# Clock_Generator.net
KiCad netlist of a schematic drawn in Altium Designer
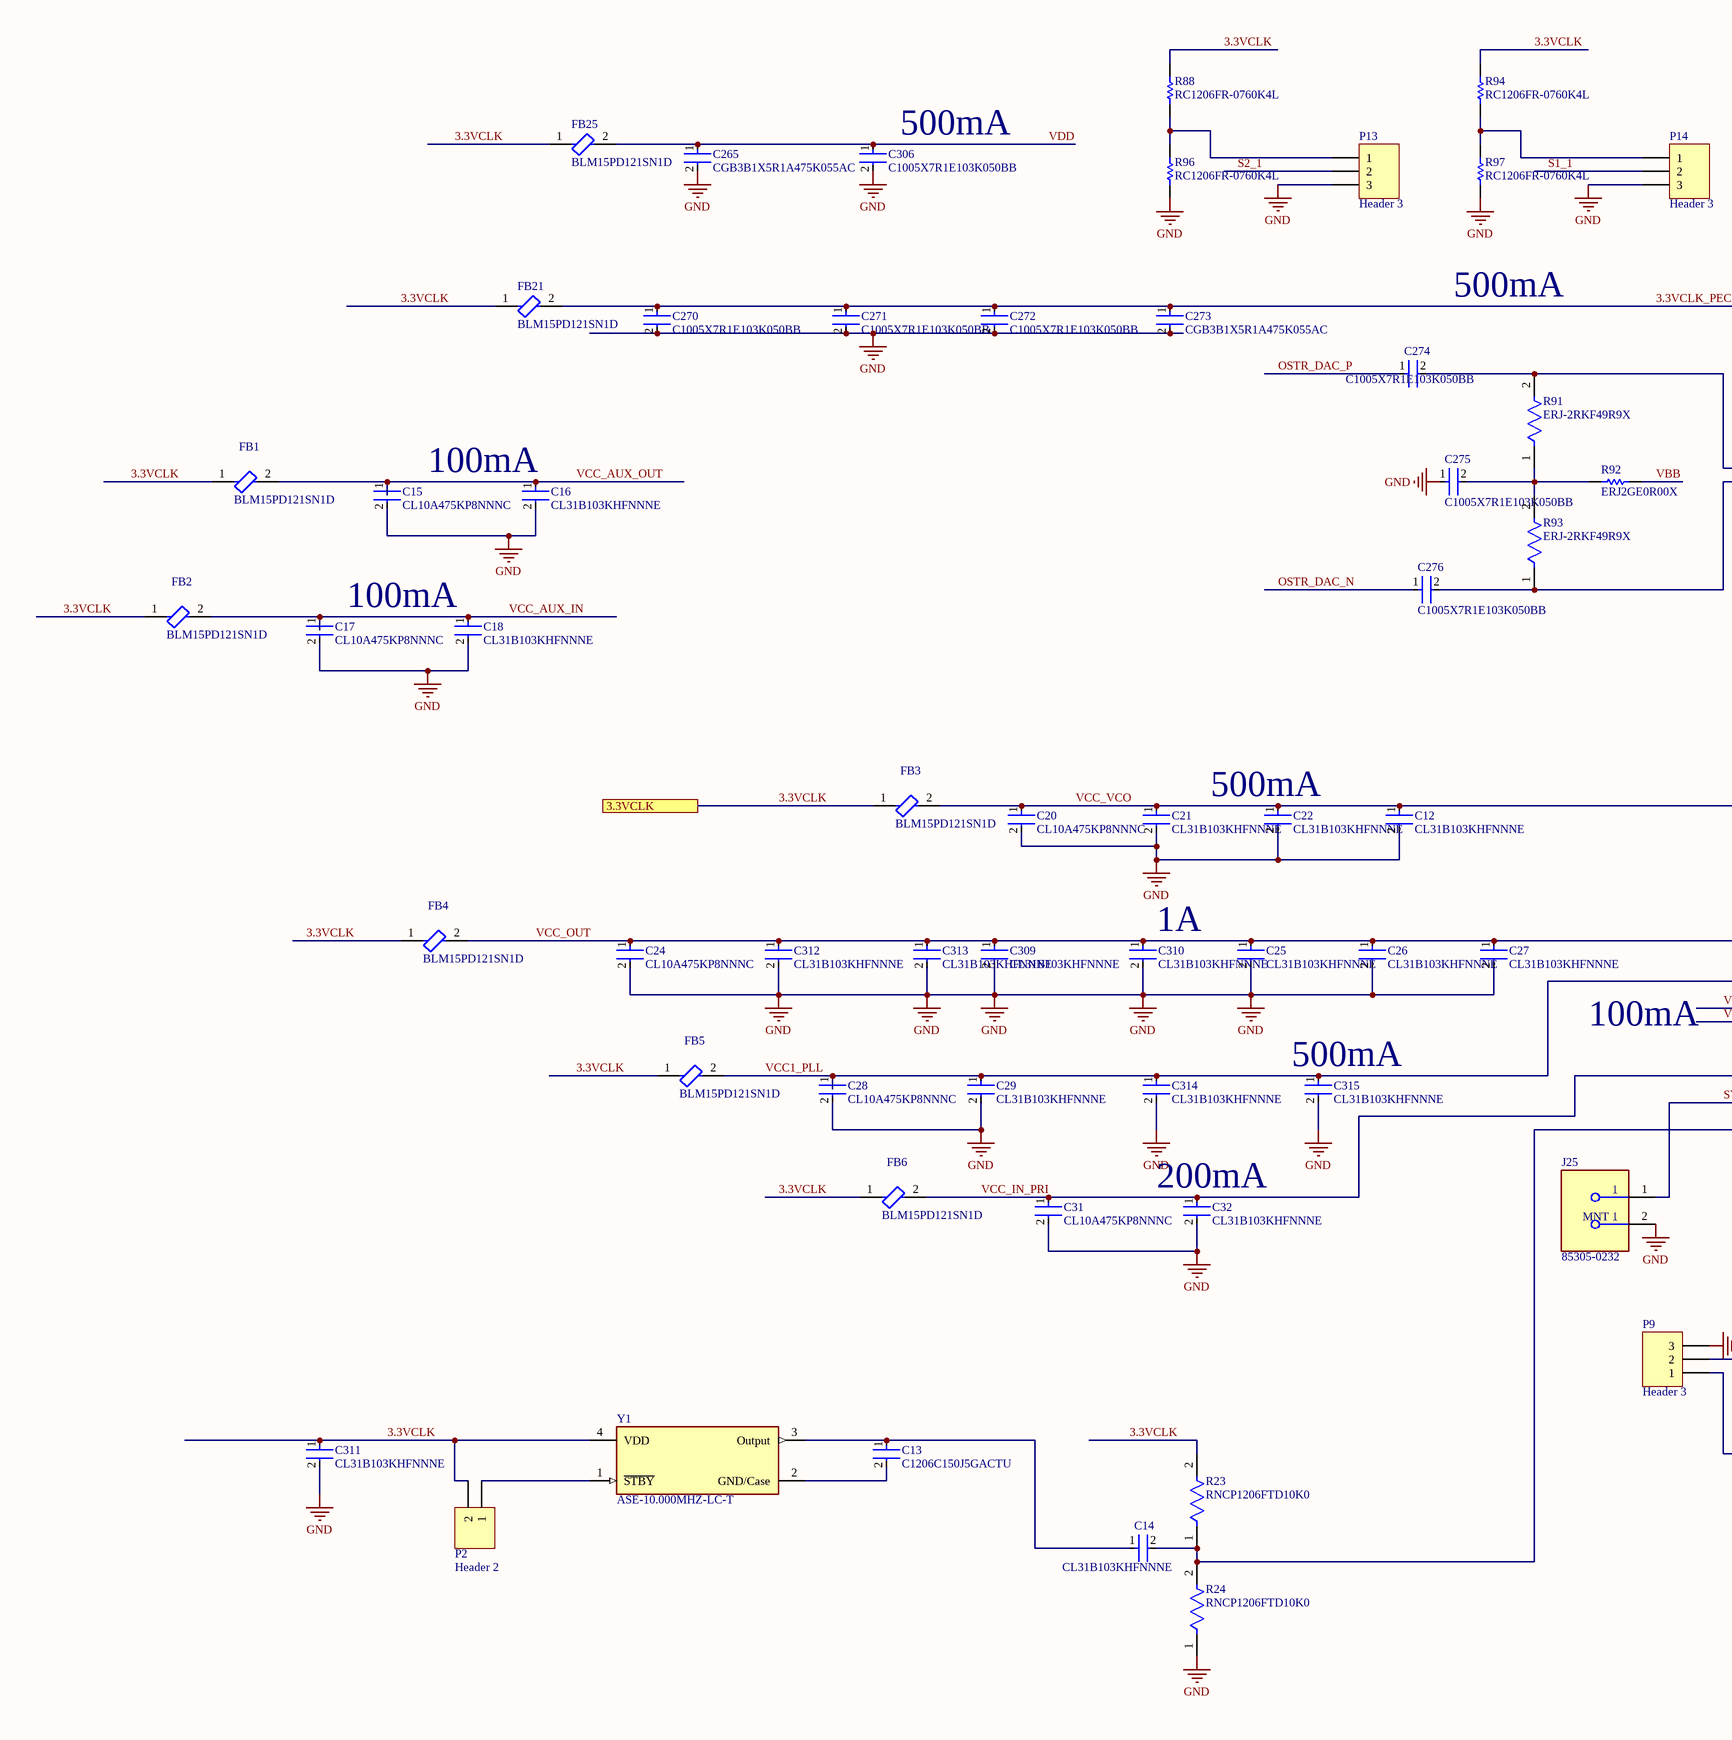
[diagram p0: Clock_Generator.SchDoc, left]
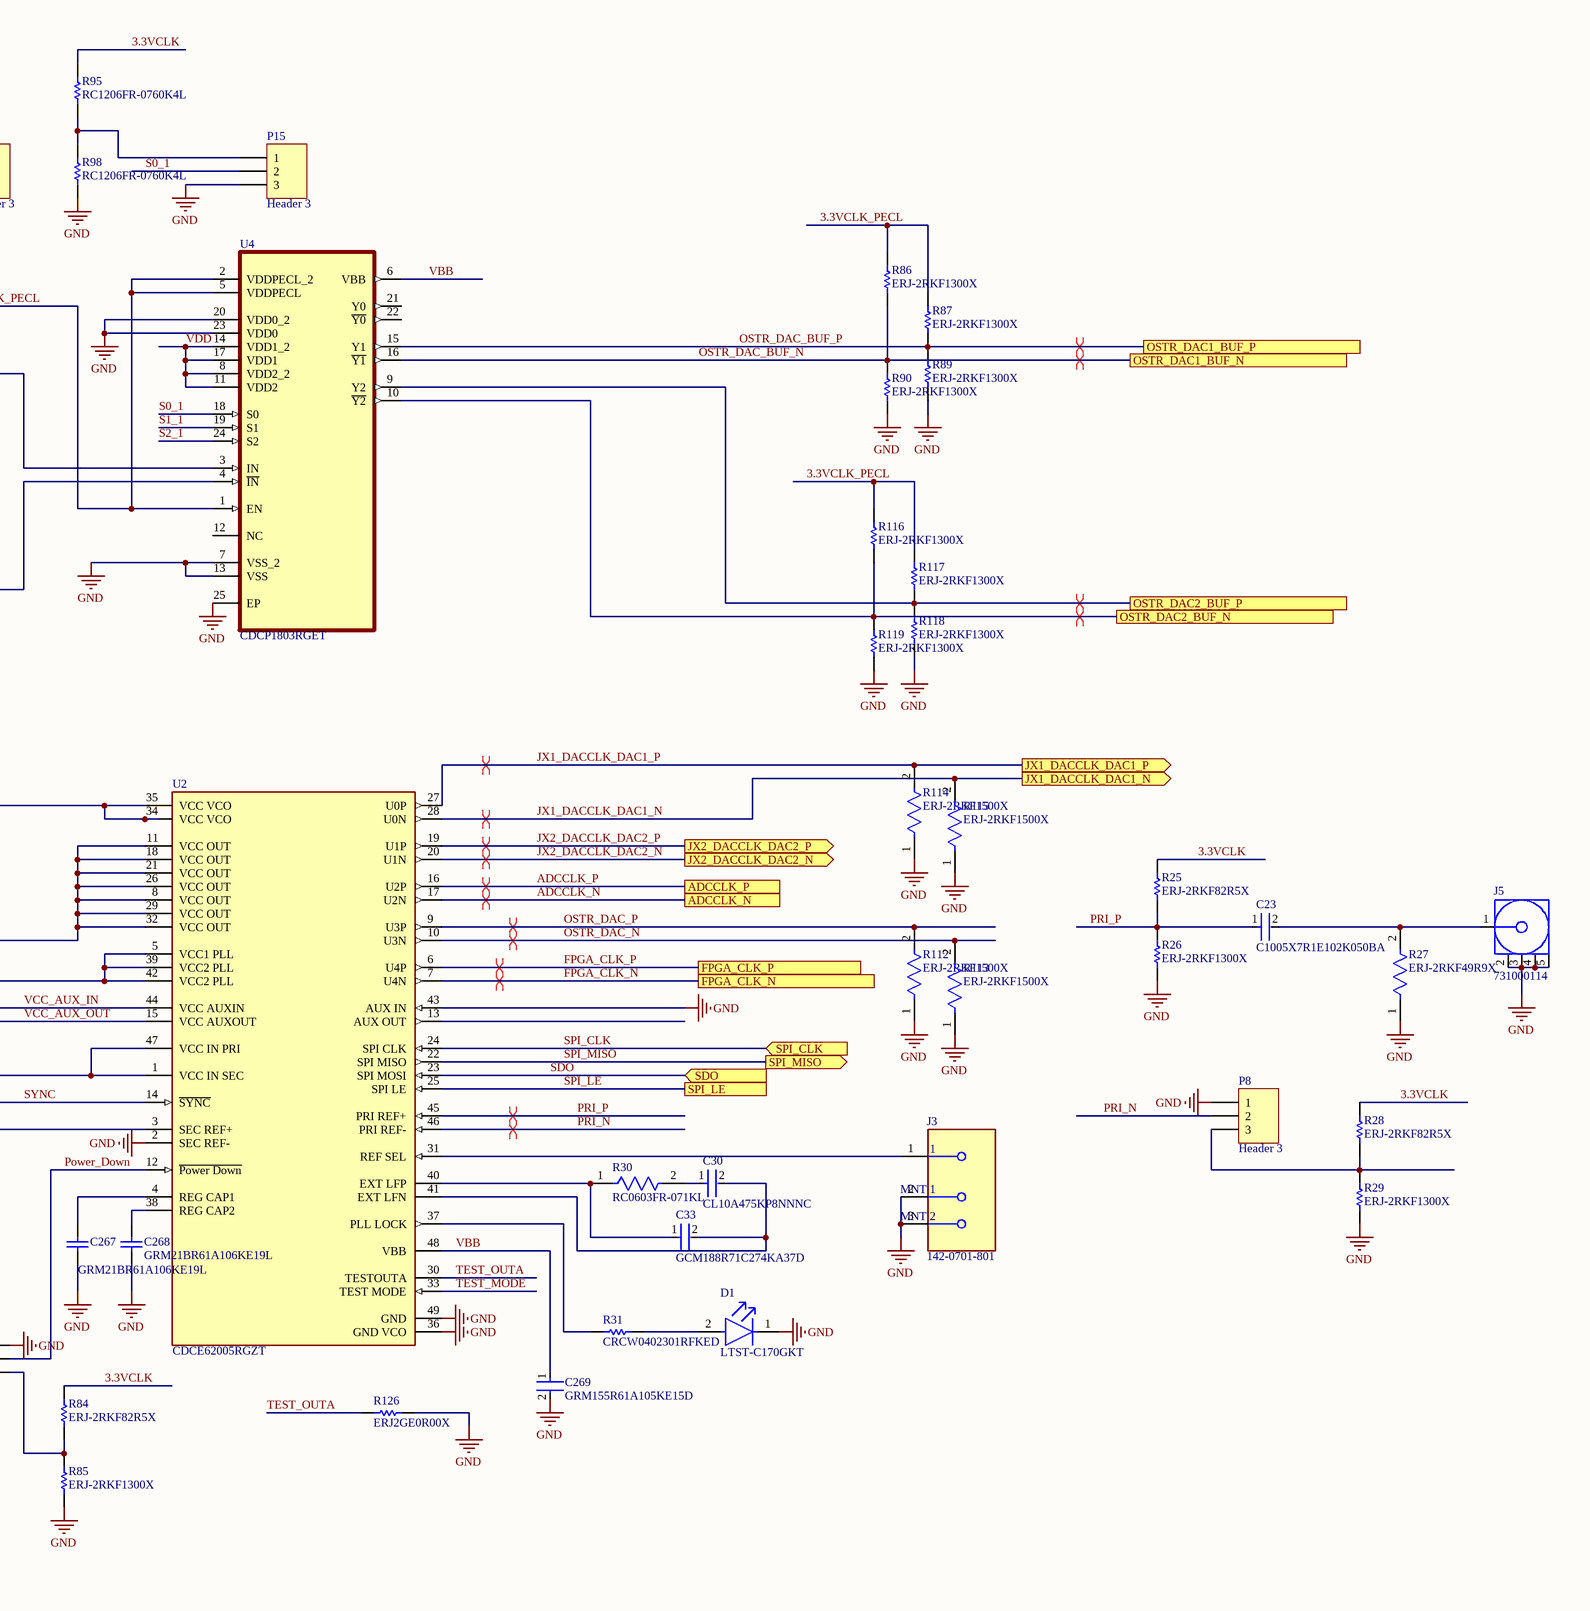
[diagram p1: Clock_Generator.SchDoc, right]

(export (version "E")
  (design (tool "Eeschema 10.0.6"))
  (components
    (comp (ref "C12")
      (value "CL31B103KHFNNNE")
      (footprint "C1206")
      (description "Cap Ceramic 10nF 630V X7R ±10% SMD 1206 +125°C Embossed T/R")
      (fields (field (name "TOLERANCE") "10%") (field (name "VOLTAGE") "630V"))
      (libsource (lib "DACֹֹ_Sources") (part "b4654b650e69147ec39a6b967a45e02"))
    )
    (comp (ref "C13")
      (value "C1206C150J5GACTU")
      (footprint "C1206")
      (description "1206 C 15pF Ceramic Multilayer Capacitor; 50 VDC; +125degC; C0G Dielec; +/-5%")
      (fields (field (name "TOLERANCE") "0.05") (field (name "MANUFACTURER") "KEMET"))
      (libsource (lib "DACֹֹ_Sources") (part "b4654b650e69147ec39a6b967a45e02"))
    )
    (comp (ref "C14")
      (value "CL31B103KHFNNNE")
      (footprint "C1206")
      (description "Cap Ceramic 10nF 630V X7R ±10% SMD 1206 +125°C Embossed T/R")
      (fields (field (name "TOLERANCE") "10%") (field (name "VOLTAGE") "630V"))
      (libsource (lib "DACֹֹ_Sources") (part "b4654b650e69147ec39a6b967a45e02"))
    )
    (comp (ref "C15")
      (value "CL10A475KP8NNNC")
      (footprint "C0603")
      (description "Cap Ceramic 4.7uF 10V X5R ±10% Pad SMD 0603 +85°C T/R")
      (fields (field (name "TOLERANCE") "10%"))
      (libsource (lib "DACֹֹ_Sources") (part "b4654b650e69147ec39a6b967a45e02"))
    )
    (comp (ref "C16")
      (value "CL31B103KHFNNNE")
      (footprint "C1206")
      (description "Cap Ceramic 10nF 630V X7R ±10% SMD 1206 +125°C Embossed T/R")
      (fields (field (name "TOLERANCE") "10%") (field (name "VOLTAGE") "630V"))
      (libsource (lib "DACֹֹ_Sources") (part "b4654b650e69147ec39a6b967a45e02"))
    )
    (comp (ref "C17")
      (value "CL10A475KP8NNNC")
      (footprint "C0603")
      (description "Cap Ceramic 4.7uF 10V X5R ±10% Pad SMD 0603 +85°C T/R")
      (fields (field (name "TOLERANCE") "10%"))
      (libsource (lib "DACֹֹ_Sources") (part "b4654b650e69147ec39a6b967a45e02"))
    )
    (comp (ref "C18")
      (value "CL31B103KHFNNNE")
      (footprint "C1206")
      (description "Cap Ceramic 10nF 630V X7R ±10% SMD 1206 +125°C Embossed T/R")
      (fields (field (name "TOLERANCE") "10%") (field (name "VOLTAGE") "630V"))
      (libsource (lib "DACֹֹ_Sources") (part "b4654b650e69147ec39a6b967a45e02"))
    )
    (comp (ref "C20")
      (value "CL10A475KP8NNNC")
      (footprint "C0603")
      (description "Cap Ceramic 4.7uF 10V X5R ±10% Pad SMD 0603 +85°C T/R")
      (fields (field (name "TOLERANCE") "10%"))
      (libsource (lib "DACֹֹ_Sources") (part "b4654b650e69147ec39a6b967a45e02"))
    )
    (comp (ref "C21")
      (value "CL31B103KHFNNNE")
      (footprint "C1206")
      (description "Cap Ceramic 10nF 630V X7R ±10% SMD 1206 +125°C Embossed T/R")
      (fields (field (name "TOLERANCE") "10%") (field (name "VOLTAGE") "630V"))
      (libsource (lib "DACֹֹ_Sources") (part "b4654b650e69147ec39a6b967a45e02"))
    )
    (comp (ref "C22")
      (value "CL31B103KHFNNNE")
      (footprint "C1206")
      (description "Cap Ceramic 10nF 630V X7R ±10% SMD 1206 +125°C Embossed T/R")
      (fields (field (name "TOLERANCE") "10%") (field (name "VOLTAGE") "630V"))
      (libsource (lib "DACֹֹ_Sources") (part "b4654b650e69147ec39a6b967a45e02"))
    )
    (comp (ref "C23")
      (value "C1005X7R1E102K050BA")
      (footprint "C0402")
      (description "Multilayer Ceramic Capacitors 1nF ±10% 25V X7R SMD 0402")
      (fields (field (name "TOLERANCE") "10%"))
      (libsource (lib "DACֹֹ_Sources") (part "b4654b650e69147ec39a6b967a45e02"))
    )
    (comp (ref "C24")
      (value "CL10A475KP8NNNC")
      (footprint "C0603")
      (description "Cap Ceramic 4.7uF 10V X5R ±10% Pad SMD 0603 +85°C T/R")
      (fields (field (name "TOLERANCE") "10%"))
      (libsource (lib "DACֹֹ_Sources") (part "b4654b650e69147ec39a6b967a45e02"))
    )
    (comp (ref "C25")
      (value "CL31B103KHFNNNE")
      (footprint "C1206")
      (description "Cap Ceramic 10nF 630V X7R ±10% SMD 1206 +125°C Embossed T/R")
      (fields (field (name "TOLERANCE") "10%") (field (name "VOLTAGE") "630V"))
      (libsource (lib "DACֹֹ_Sources") (part "b4654b650e69147ec39a6b967a45e02"))
    )
    (comp (ref "C26")
      (value "CL31B103KHFNNNE")
      (footprint "C1206")
      (description "Cap Ceramic 10nF 630V X7R ±10% SMD 1206 +125°C Embossed T/R")
      (fields (field (name "TOLERANCE") "10%") (field (name "VOLTAGE") "630V"))
      (libsource (lib "DACֹֹ_Sources") (part "b4654b650e69147ec39a6b967a45e02"))
    )
    (comp (ref "C27")
      (value "CL31B103KHFNNNE")
      (footprint "C1206")
      (description "Cap Ceramic 10nF 630V X7R ±10% SMD 1206 +125°C Embossed T/R")
      (fields (field (name "TOLERANCE") "10%") (field (name "VOLTAGE") "630V"))
      (libsource (lib "DACֹֹ_Sources") (part "b4654b650e69147ec39a6b967a45e02"))
    )
    (comp (ref "C28")
      (value "CL10A475KP8NNNC")
      (footprint "C0603")
      (description "Cap Ceramic 4.7uF 10V X5R ±10% Pad SMD 0603 +85°C T/R")
      (fields (field (name "TOLERANCE") "10%"))
      (libsource (lib "DACֹֹ_Sources") (part "b4654b650e69147ec39a6b967a45e02"))
    )
    (comp (ref "C29")
      (value "CL31B103KHFNNNE")
      (footprint "C1206")
      (description "Cap Ceramic 10nF 630V X7R ±10% SMD 1206 +125°C Embossed T/R")
      (fields (field (name "TOLERANCE") "10%") (field (name "VOLTAGE") "630V"))
      (libsource (lib "DACֹֹ_Sources") (part "b4654b650e69147ec39a6b967a45e02"))
    )
    (comp (ref "C30")
      (value "CL10A475KP8NNNC")
      (footprint "C0603")
      (description "Cap Ceramic 4.7uF 10V X5R ±10% Pad SMD 0603 +85°C T/R")
      (fields (field (name "TOLERANCE") "10%"))
      (libsource (lib "DACֹֹ_Sources") (part "b4654b650e69147ec39a6b967a45e02"))
    )
    (comp (ref "C31")
      (value "CL10A475KP8NNNC")
      (footprint "C0603")
      (description "Cap Ceramic 4.7uF 10V X5R ±10% Pad SMD 0603 +85°C T/R")
      (fields (field (name "TOLERANCE") "10%"))
      (libsource (lib "DACֹֹ_Sources") (part "b4654b650e69147ec39a6b967a45e02"))
    )
    (comp (ref "C32")
      (value "CL31B103KHFNNNE")
      (footprint "C1206")
      (description "Cap Ceramic 10nF 630V X7R ±10% SMD 1206 +125°C Embossed T/R")
      (fields (field (name "TOLERANCE") "10%") (field (name "VOLTAGE") "630V"))
      (libsource (lib "DACֹֹ_Sources") (part "b4654b650e69147ec39a6b967a45e02"))
    )
    (comp (ref "C33")
      (value "GCM188R71C274KA37D")
      (footprint "C0603")
      (description "Ceramic Capacitor for Automotive 270nF  ±10% 16VDC X7R 0603 Paper T/R")
      (fields (field (name "TOLERANCE") "10%"))
      (libsource (lib "DACֹֹ_Sources") (part "02cd4be3c70576c341d710602a673aa"))
    )
    (comp (ref "C265")
      (value "CGB3B1X5R1A475K055AC")
      (footprint "C0603")
      (description "CAP CER 4.7UF 10V X5R 0603")
      (fields (field (name "TOLERANCE") "10%"))
      (libsource (lib "DACֹֹ_Sources") (part "b4654b650e69147ec39a6b967a45e02"))
    )
    (comp (ref "C267")
      (value "GRM21BR61A106KE19L")
      (footprint "C0805")
      (description "CAP, Ceramic, 10 uF, 10%, 10 V, 0805, RoHS, Tape and Reel")
      (fields (field (name "MANUFACTURER") "Murata") (field (name "TOLERANCE") "±10%"))
      (libsource (lib "DACֹֹ_Sources") (part "CAP-NP-2"))
    )
    (comp (ref "C268")
      (value "GRM21BR61A106KE19L")
      (footprint "C0805")
      (description "CAP, Ceramic, 10 uF, 10%, 10 V, 0805, RoHS, Tape and Reel")
      (fields (field (name "MANUFACTURER") "Murata") (field (name "TOLERANCE") "±10%"))
      (libsource (lib "DACֹֹ_Sources") (part "CAP-NP-2"))
    )
    (comp (ref "C269")
      (value "GRM155R61A105KE15D")
      (footprint "C0402")
      (description "CAP CER 1UF 10V X5R 0402")
      (fields
        (field (name "OCTOPART") "https://octopart.com/grm155r61a105ke15d-murata-197442")
        (field (name "MANUFACTURER") "Murata")
      )
      (libsource (lib "DACֹֹ_Sources") (part "02cd4be3c70576c341d710602a673aa"))
    )
    (comp (ref "C270")
      (value "C1005X7R1E103K050BB")
      (footprint "C0402")
      (description "Multilayer Ceramic Capacitors 10nF ±10% 25V X7R SMD 0402")
      (fields (field (name "TOLERANCE") "10%") (field (name "VOLTAGE") "25V"))
      (libsource (lib "DACֹֹ_Sources") (part "b4654b650e69147ec39a6b967a45e02"))
    )
    (comp (ref "C271")
      (value "C1005X7R1E103K050BB")
      (footprint "C0402")
      (description "Multilayer Ceramic Capacitors 10nF ±10% 25V X7R SMD 0402")
      (fields (field (name "TOLERANCE") "10%") (field (name "VOLTAGE") "25V"))
      (libsource (lib "DACֹֹ_Sources") (part "b4654b650e69147ec39a6b967a45e02"))
    )
    (comp (ref "C272")
      (value "C1005X7R1E103K050BB")
      (footprint "C0402")
      (description "Multilayer Ceramic Capacitors 10nF ±10% 25V X7R SMD 0402")
      (fields (field (name "TOLERANCE") "10%") (field (name "VOLTAGE") "25V"))
      (libsource (lib "DACֹֹ_Sources") (part "b4654b650e69147ec39a6b967a45e02"))
    )
    (comp (ref "C273")
      (value "CGB3B1X5R1A475K055AC")
      (footprint "C0603")
      (description "CAP CER 4.7UF 10V X5R 0603")
      (fields (field (name "TOLERANCE") "10%"))
      (libsource (lib "DACֹֹ_Sources") (part "b4654b650e69147ec39a6b967a45e02"))
    )
    (comp (ref "C274")
      (value "C1005X7R1E103K050BB")
      (footprint "C0402")
      (description "Multilayer Ceramic Capacitors 10nF ±10% 25V X7R SMD 0402")
      (fields (field (name "TOLERANCE") "10%") (field (name "VOLTAGE") "25V"))
      (libsource (lib "DACֹֹ_Sources") (part "b4654b650e69147ec39a6b967a45e02"))
    )
    (comp (ref "C275")
      (value "C1005X7R1E103K050BB")
      (footprint "C0402")
      (description "Multilayer Ceramic Capacitors 10nF ±10% 25V X7R SMD 0402")
      (fields (field (name "TOLERANCE") "10%") (field (name "VOLTAGE") "25V"))
      (libsource (lib "DACֹֹ_Sources") (part "b4654b650e69147ec39a6b967a45e02"))
    )
    (comp (ref "C276")
      (value "C1005X7R1E103K050BB")
      (footprint "C0402")
      (description "Multilayer Ceramic Capacitors 10nF ±10% 25V X7R SMD 0402")
      (fields (field (name "TOLERANCE") "10%") (field (name "VOLTAGE") "25V"))
      (libsource (lib "DACֹֹ_Sources") (part "b4654b650e69147ec39a6b967a45e02"))
    )
    (comp (ref "C306")
      (value "C1005X7R1E103K050BB")
      (footprint "C0402")
      (description "Multilayer Ceramic Capacitors 10nF ±10% 25V X7R SMD 0402")
      (fields (field (name "TOLERANCE") "10%") (field (name "VOLTAGE") "25V"))
      (libsource (lib "DACֹֹ_Sources") (part "b4654b650e69147ec39a6b967a45e02"))
    )
    (comp (ref "C309")
      (value "CL31B103KHFNNNE")
      (footprint "C1206")
      (description "Cap Ceramic 10nF 630V X7R ±10% SMD 1206 +125°C Embossed T/R")
      (fields (field (name "TOLERANCE") "10%") (field (name "VOLTAGE") "630V"))
      (libsource (lib "DACֹֹ_Sources") (part "b4654b650e69147ec39a6b967a45e02"))
    )
    (comp (ref "C310")
      (value "CL31B103KHFNNNE")
      (footprint "C1206")
      (description "Cap Ceramic 10nF 630V X7R ±10% SMD 1206 +125°C Embossed T/R")
      (fields (field (name "TOLERANCE") "10%") (field (name "VOLTAGE") "630V"))
      (libsource (lib "DACֹֹ_Sources") (part "b4654b650e69147ec39a6b967a45e02"))
    )
    (comp (ref "C311")
      (value "CL31B103KHFNNNE")
      (footprint "C1206")
      (description "Cap Ceramic 10nF 630V X7R ±10% SMD 1206 +125°C Embossed T/R")
      (fields (field (name "TOLERANCE") "10%") (field (name "VOLTAGE") "630V"))
      (libsource (lib "DACֹֹ_Sources") (part "b4654b650e69147ec39a6b967a45e02"))
    )
    (comp (ref "C312")
      (value "CL31B103KHFNNNE")
      (footprint "C1206")
      (description "Cap Ceramic 10nF 630V X7R ±10% SMD 1206 +125°C Embossed T/R")
      (fields (field (name "TOLERANCE") "10%") (field (name "VOLTAGE") "630V"))
      (libsource (lib "DACֹֹ_Sources") (part "b4654b650e69147ec39a6b967a45e02"))
    )
    (comp (ref "C313")
      (value "CL31B103KHFNNNE")
      (footprint "C1206")
      (description "Cap Ceramic 10nF 630V X7R ±10% SMD 1206 +125°C Embossed T/R")
      (fields (field (name "TOLERANCE") "10%") (field (name "VOLTAGE") "630V"))
      (libsource (lib "DACֹֹ_Sources") (part "b4654b650e69147ec39a6b967a45e02"))
    )
    (comp (ref "C314")
      (value "CL31B103KHFNNNE")
      (footprint "C1206")
      (description "Cap Ceramic 10nF 630V X7R ±10% SMD 1206 +125°C Embossed T/R")
      (fields (field (name "TOLERANCE") "10%") (field (name "VOLTAGE") "630V"))
      (libsource (lib "DACֹֹ_Sources") (part "b4654b650e69147ec39a6b967a45e02"))
    )
    (comp (ref "C315")
      (value "CL31B103KHFNNNE")
      (footprint "C1206")
      (description "Cap Ceramic 10nF 630V X7R ±10% SMD 1206 +125°C Embossed T/R")
      (fields (field (name "TOLERANCE") "10%") (field (name "VOLTAGE") "630V"))
      (libsource (lib "DACֹֹ_Sources") (part "b4654b650e69147ec39a6b967a45e02"))
    )
    (comp (ref "D1")
      (value "LTST-C170GKT")
      (footprint "FP-LTST-C170GKT-MFG")
      (description "LED GREEN CLEAR SMD")
      (fields (field (name "VOLTAGE") "5V"))
      (libsource (lib "DACֹֹ_Sources") (part "8706943c75ba83719d021d2fdc84c58"))
    )
    (comp (ref "FB1")
      (value "BLM15PD121SN1D")
      (footprint "BLM15")
      (description "Chip Ferrite Bead, 0402, 120Ω @ 100MHz, 0.09Ω, 25%, 1.3A")
      (fields (field (name "TOLERANCE") "25%"))
      (libsource (lib "DACֹֹ_Sources") (part "5f30dd21d616792df468990f7003faa"))
    )
    (comp (ref "FB2")
      (value "BLM15PD121SN1D")
      (footprint "BLM15")
      (description "Chip Ferrite Bead, 0402, 120Ω @ 100MHz, 0.09Ω, 25%, 1.3A")
      (fields (field (name "TOLERANCE") "25%"))
      (libsource (lib "DACֹֹ_Sources") (part "5f30dd21d616792df468990f7003faa"))
    )
    (comp (ref "FB3")
      (value "BLM15PD121SN1D")
      (footprint "BLM15")
      (description "Chip Ferrite Bead, 0402, 120Ω @ 100MHz, 0.09Ω, 25%, 1.3A")
      (fields (field (name "TOLERANCE") "25%"))
      (libsource (lib "DACֹֹ_Sources") (part "5f30dd21d616792df468990f7003faa"))
    )
    (comp (ref "FB4")
      (value "BLM15PD121SN1D")
      (footprint "BLM15")
      (description "Chip Ferrite Bead, 0402, 120Ω @ 100MHz, 0.09Ω, 25%, 1.3A")
      (fields (field (name "TOLERANCE") "25%"))
      (libsource (lib "DACֹֹ_Sources") (part "5f30dd21d616792df468990f7003faa"))
    )
    (comp (ref "FB5")
      (value "BLM15PD121SN1D")
      (footprint "BLM15")
      (description "Chip Ferrite Bead, 0402, 120Ω @ 100MHz, 0.09Ω, 25%, 1.3A")
      (fields (field (name "TOLERANCE") "25%"))
      (libsource (lib "DACֹֹ_Sources") (part "5f30dd21d616792df468990f7003faa"))
    )
    (comp (ref "FB6")
      (value "BLM15PD121SN1D")
      (footprint "BLM15")
      (description "Chip Ferrite Bead, 0402, 120Ω @ 100MHz, 0.09Ω, 25%, 1.3A")
      (fields (field (name "TOLERANCE") "25%"))
      (libsource (lib "DACֹֹ_Sources") (part "5f30dd21d616792df468990f7003faa"))
    )
    (comp (ref "FB21")
      (value "BLM15PD121SN1D")
      (footprint "BLM15")
      (description "Chip Ferrite Bead, 0402, 120Ω @ 100MHz, 0.09Ω, 25%, 1.3A")
      (fields (field (name "TOLERANCE") "25%"))
      (libsource (lib "DACֹֹ_Sources") (part "5f30dd21d616792df468990f7003faa"))
    )
    (comp (ref "FB25")
      (value "BLM15PD121SN1D")
      (footprint "BLM15")
      (description "Chip Ferrite Bead, 0402, 120Ω @ 100MHz, 0.09Ω, 25%, 1.3A")
      (fields (field (name "TOLERANCE") "25%"))
      (libsource (lib "DACֹֹ_Sources") (part "5f30dd21d616792df468990f7003faa"))
    )
    (comp (ref "J3")
      (value "142-0701-801")
      (footprint "FP-142-0701-801-MFG")
      (description "CONN SMA JACK STR 50OHM EDGE MNT")
      (libsource (lib "DACֹֹ_Sources") (part "89929399afe843c8b6880c6cbd0f99a"))
    )
    (comp (ref "J5")
      (value "731000114")
      (footprint "MOLX-731000114_V")
      (description "SMA Right-Angle PCB Jack Receptacle, Brass Body, Gold Plated, 50 Ohm, 5-Pin THD, RoHS, Tray")
      (fields (field (name "MANUFACTURER") "Molex"))
      (libsource (lib "DACֹֹ_Sources") (part "CN-S-4F-RF5"))
    )
    (comp (ref "J25")
      (value "85305-0232")
      (footprint "FP-85305-0232-MFG")
      (description "CONN SMP PLUG STR 50 OHM SMD")
      (libsource (lib "DACֹֹ_Sources") (part "d2a53f3a980517e545f22a6fb6569cc"))
    )
    (comp (ref "P2")
      (value "Header 2")
      (footprint "HEADER_2X1")
      (description "Header, 2-Pin")
      (fields (field (name "PUBLISHER") "Altium Limited"))
      (libsource (lib "DACֹֹ_Sources") (part "Header 2"))
    )
    (comp (ref "P8")
      (value "Header 3")
      (footprint "HEADER_3X1")
      (description "Header, 3-Pin")
      (fields (field (name "PUBLISHER") "Altium Limited"))
      (libsource (lib "") (part "Header 3_1"))
    )
    (comp (ref "P9")
      (value "Header 3")
      (footprint "HEADER_3X1")
      (description "Header, 3-Pin")
      (fields (field (name "PUBLISHER") "Altium Limited"))
      (libsource (lib "DACֹֹ_Sources") (part "Header 3"))
    )
    (comp (ref "P13")
      (value "Header 3")
      (footprint "HEADER_3X1")
      (description "Header, 3-Pin")
      (fields (field (name "PUBLISHER") "Altium Limited"))
      (libsource (lib "") (part "Header 3_1"))
    )
    (comp (ref "P14")
      (value "Header 3")
      (footprint "HEADER_3X1")
      (description "Header, 3-Pin")
      (fields (field (name "PUBLISHER") "Altium Limited"))
      (libsource (lib "") (part "Header 3_1"))
    )
    (comp (ref "P15")
      (value "Header 3")
      (footprint "HEADER_3X1")
      (description "Header, 3-Pin")
      (fields (field (name "PUBLISHER") "Altium Limited"))
      (libsource (lib "") (part "Header 3_1"))
    )
    (comp (ref "R23")
      (value "RNCP1206FTD10K0")
      (footprint "R1206")
      (description "10kΩ ±1% 0.5W 1206 High Power Anti-Sulfur Thin Film Chip Resistor")
      (fields (field (name "TOLERANCE") "1%"))
      (libsource (lib "DACֹֹ_Sources") (part "1029c3af85768c4190bb7ad29bc67b5"))
    )
    (comp (ref "R24")
      (value "RNCP1206FTD10K0")
      (footprint "R1206")
      (description "10kΩ ±1% 0.5W 1206 High Power Anti-Sulfur Thin Film Chip Resistor")
      (fields (field (name "TOLERANCE") "1%"))
      (libsource (lib "DACֹֹ_Sources") (part "1029c3af85768c4190bb7ad29bc67b5"))
    )
    (comp (ref "R25")
      (value "ERJ-2RKF82R5X")
      (footprint "R0402")
      (fields (field (name "MANUFACTURER") "Panasonic"))
      (libsource (lib "DACֹֹ_Sources") (part "RES"))
    )
    (comp (ref "R26")
      (value "ERJ-2RKF1300X")
      (footprint "R0402")
      (fields (field (name "MANUFACTURER") "Panasonic"))
      (libsource (lib "DACֹֹ_Sources") (part "RES"))
    )
    (comp (ref "R27")
      (value "ERJ-2RKF49R9X")
      (footprint "R0402")
      (description "RES SMD 49.9 OHM 1% 1/10W 0402")
      (fields (field (name "TOLERANCE") "1%"))
      (libsource (lib "DACֹֹ_Sources") (part "8db39607336c341a927600551d01821"))
    )
    (comp (ref "R28")
      (value "ERJ-2RKF82R5X")
      (footprint "R0402")
      (fields (field (name "MANUFACTURER") "Panasonic"))
      (libsource (lib "DACֹֹ_Sources") (part "RES"))
    )
    (comp (ref "R29")
      (value "ERJ-2RKF1300X")
      (footprint "R0402")
      (fields (field (name "MANUFACTURER") "Panasonic"))
      (libsource (lib "DACֹֹ_Sources") (part "RES"))
    )
    (comp (ref "R30")
      (value "RC0603FR-071KL")
      (footprint "R0603")
      (description "RES 1K OHM 1% 1/10W 0603")
      (fields (field (name "TOLERANCE") "1%"))
      (libsource (lib "DACֹֹ_Sources") (part "1029c3af85768c4190bb7ad29bc67b5"))
    )
    (comp (ref "R31")
      (value "CRCW0402301RFKED")
      (footprint "R0402")
      (fields (field (name "MANUFACTURER") "Vishay Dale"))
      (libsource (lib "DACֹֹ_Sources") (part "RES"))
    )
    (comp (ref "R84")
      (value "ERJ-2RKF82R5X")
      (footprint "R0402")
      (fields (field (name "MANUFACTURER") "Panasonic"))
      (libsource (lib "DACֹֹ_Sources") (part "RES"))
    )
    (comp (ref "R85")
      (value "ERJ-2RKF1300X")
      (footprint "R0402")
      (fields (field (name "MANUFACTURER") "Panasonic"))
      (libsource (lib "DACֹֹ_Sources") (part "RES"))
    )
    (comp (ref "R86")
      (value "ERJ-2RKF1300X")
      (footprint "R0402")
      (fields (field (name "MANUFACTURER") "Panasonic"))
      (libsource (lib "DACֹֹ_Sources") (part "RES"))
    )
    (comp (ref "R87")
      (value "ERJ-2RKF1300X")
      (footprint "R0402")
      (fields (field (name "MANUFACTURER") "Panasonic"))
      (libsource (lib "DACֹֹ_Sources") (part "RES"))
    )
    (comp (ref "R88")
      (value "RC1206FR-0760K4L")
      (footprint "R1206")
      (fields (field (name "MANUFACTURER") "Yageo"))
      (libsource (lib "DACֹֹ_Sources") (part "RES"))
    )
    (comp (ref "R89")
      (value "ERJ-2RKF1300X")
      (footprint "R0402")
      (fields (field (name "MANUFACTURER") "Panasonic"))
      (libsource (lib "DACֹֹ_Sources") (part "RES"))
    )
    (comp (ref "R90")
      (value "ERJ-2RKF1300X")
      (footprint "R0402")
      (fields (field (name "MANUFACTURER") "Panasonic"))
      (libsource (lib "DACֹֹ_Sources") (part "RES"))
    )
    (comp (ref "R91")
      (value "ERJ-2RKF49R9X")
      (footprint "R0402")
      (description "RES SMD 49.9 OHM 1% 1/10W 0402")
      (fields (field (name "TOLERANCE") "1%"))
      (libsource (lib "DACֹֹ_Sources") (part "8db39607336c341a927600551d01821"))
    )
    (comp (ref "R92")
      (value "ERJ2GE0R00X")
      (footprint "R0402")
      (description "Chip Resistor, 0 Ohm, 0.1 W, -55 to 155 degC, 0402 (1005 Metric), RoHS, Tape and Reel")
      (fields (field (name "MANUFACTURER") "Panasonic") (field (name "TOLERANCE") "5%"))
      (libsource (lib "DACֹֹ_Sources") (part "RES-2"))
    )
    (comp (ref "R93")
      (value "ERJ-2RKF49R9X")
      (footprint "R0402")
      (description "RES SMD 49.9 OHM 1% 1/10W 0402")
      (fields (field (name "TOLERANCE") "1%"))
      (libsource (lib "DACֹֹ_Sources") (part "8db39607336c341a927600551d01821"))
    )
    (comp (ref "R94")
      (value "RC1206FR-0760K4L")
      (footprint "R1206")
      (fields (field (name "MANUFACTURER") "Yageo"))
      (libsource (lib "DACֹֹ_Sources") (part "RES"))
    )
    (comp (ref "R95")
      (value "RC1206FR-0760K4L")
      (footprint "R1206")
      (fields (field (name "MANUFACTURER") "Yageo"))
      (libsource (lib "DACֹֹ_Sources") (part "RES"))
    )
    (comp (ref "R96")
      (value "RC1206FR-0760K4L")
      (footprint "R1206")
      (fields (field (name "MANUFACTURER") "Yageo"))
      (libsource (lib "DACֹֹ_Sources") (part "RES"))
    )
    (comp (ref "R97")
      (value "RC1206FR-0760K4L")
      (footprint "R1206")
      (fields (field (name "MANUFACTURER") "Yageo"))
      (libsource (lib "DACֹֹ_Sources") (part "RES"))
    )
    (comp (ref "R98")
      (value "RC1206FR-0760K4L")
      (footprint "R1206")
      (fields (field (name "MANUFACTURER") "Yageo"))
      (libsource (lib "DACֹֹ_Sources") (part "RES"))
    )
    (comp (ref "R112")
      (value "ERJ-2RKF1500X")
      (footprint "R0402")
      (description "RES SMD 150 OHM 1% 1/10W 0402")
      (fields (field (name "TOLERANCE") "1%"))
      (libsource (lib "DACֹֹ_Sources") (part "1029c3af85768c4190bb7ad29bc67b5"))
    )
    (comp (ref "R113")
      (value "ERJ-2RKF1500X")
      (footprint "R0402")
      (description "RES SMD 150 OHM 1% 1/10W 0402")
      (fields (field (name "TOLERANCE") "1%"))
      (libsource (lib "DACֹֹ_Sources") (part "1029c3af85768c4190bb7ad29bc67b5"))
    )
    (comp (ref "R114")
      (value "ERJ-2RKF1500X")
      (footprint "R0402")
      (description "RES SMD 150 OHM 1% 1/10W 0402")
      (fields (field (name "TOLERANCE") "1%"))
      (libsource (lib "DACֹֹ_Sources") (part "1029c3af85768c4190bb7ad29bc67b5"))
    )
    (comp (ref "R115")
      (value "ERJ-2RKF1500X")
      (footprint "R0402")
      (description "RES SMD 150 OHM 1% 1/10W 0402")
      (fields (field (name "TOLERANCE") "1%"))
      (libsource (lib "DACֹֹ_Sources") (part "1029c3af85768c4190bb7ad29bc67b5"))
    )
    (comp (ref "R116")
      (value "ERJ-2RKF1300X")
      (footprint "R0402")
      (fields (field (name "MANUFACTURER") "Panasonic"))
      (libsource (lib "DACֹֹ_Sources") (part "RES"))
    )
    (comp (ref "R117")
      (value "ERJ-2RKF1300X")
      (footprint "R0402")
      (fields (field (name "MANUFACTURER") "Panasonic"))
      (libsource (lib "DACֹֹ_Sources") (part "RES"))
    )
    (comp (ref "R118")
      (value "ERJ-2RKF1300X")
      (footprint "R0402")
      (fields (field (name "MANUFACTURER") "Panasonic"))
      (libsource (lib "DACֹֹ_Sources") (part "RES"))
    )
    (comp (ref "R119")
      (value "ERJ-2RKF1300X")
      (footprint "R0402")
      (fields (field (name "MANUFACTURER") "Panasonic"))
      (libsource (lib "DACֹֹ_Sources") (part "RES"))
    )
    (comp (ref "R126")
      (value "ERJ2GE0R00X")
      (footprint "R0402")
      (description "Chip Resistor, 0 Ohm, 0.1 W, -55 to 155 degC, 0402 (1005 Metric), RoHS, Tape and Reel")
      (fields (field (name "MANUFACTURER") "Panasonic") (field (name "TOLERANCE") "5%"))
      (libsource (lib "DACֹֹ_Sources") (part "RES-2"))
    )
    (comp (ref "U2")
      (value "CDCE62005RGZT")
      (footprint "FP-RGZ0048D-IPC_A")
      (description "IC CLK SYNTH/JITTER CLEANR 48QFN")
      (libsource (lib "DACֹֹ_Sources") (part "79e6de338fe35b6fdc3d186d6aa1691"))
    )
    (comp (ref "U4")
      (value "CDCP1803RGET")
      (footprint "QFN25")
      (description "1:3 LVPECL clock buffer with programable divider")
      (fields (field (name "MF") "Texas Instruments"))
      (libsource (lib "DACֹֹ_Sources") (part "CDCP1803RGET"))
    )
    (comp (ref "Y1")
      (value "ASE-10.000MHZ-LC-T")
      (footprint "ASE")
      (description "XTAL Oscillator 10MHz ±50ppm CMOS 3.3V 4-SMD 3.2mm x 2.5mm")
      (libsource (lib "DACֹֹ_Sources") (part "61a724e6190563596ac712fef61ad37"))
    )
  )
  (nets
    (net (code "1") (name "/3.3VCLK") (class "Default")
      (node (ref "C311") (pin "1") (pinfunction "1_1") (pintype "passive"))
      (node (ref "FB1") (pin "1") (pinfunction "1_1") (pintype "passive"))
      (node (ref "FB2") (pin "1") (pinfunction "1_1") (pintype "passive"))
      (node (ref "FB21") (pin "1") (pinfunction "1_1") (pintype "passive"))
      (node (ref "FB25") (pin "1") (pinfunction "1_1") (pintype "passive"))
      (node (ref "FB3") (pin "1") (pinfunction "1_1") (pintype "passive"))
      (node (ref "FB4") (pin "1") (pinfunction "1_1") (pintype "passive"))
      (node (ref "FB5") (pin "1") (pinfunction "1_1") (pintype "passive"))
      (node (ref "FB6") (pin "1") (pinfunction "1_1") (pintype "passive"))
      (node (ref "P2") (pin "2") (pinfunction "2_2") (pintype "passive"))
      (node (ref "R23") (pin "2") (pinfunction "2_2") (pintype "passive"))
      (node (ref "R25") (pin "2") (pinfunction "2_2") (pintype "passive"))
      (node (ref "R28") (pin "2") (pinfunction "2_2") (pintype "passive"))
      (node (ref "R84") (pin "2") (pinfunction "2_2") (pintype "passive"))
      (node (ref "R88") (pin "2") (pinfunction "2_2") (pintype "passive"))
      (node (ref "R94") (pin "2") (pinfunction "2_2") (pintype "passive"))
      (node (ref "R95") (pin "2") (pinfunction "2_2") (pintype "passive"))
      (node (ref "Y1") (pin "4") (pinfunction "VDD_4") (pintype "power_in"))
    )
    (net (code "2") (name "/3.3VCLK_PECL") (class "Default")
      (node (ref "C270") (pin "1") (pinfunction "1_1") (pintype "passive"))
      (node (ref "C271") (pin "1") (pinfunction "1_1") (pintype "passive"))
      (node (ref "C272") (pin "1") (pinfunction "1_1") (pintype "passive"))
      (node (ref "C273") (pin "1") (pinfunction "1_1") (pintype "passive"))
      (node (ref "FB21") (pin "2") (pinfunction "2_2") (pintype "passive"))
      (node (ref "R116") (pin "2") (pinfunction "2_2") (pintype "passive"))
      (node (ref "R117") (pin "2") (pinfunction "2_2") (pintype "passive"))
      (node (ref "R86") (pin "2") (pinfunction "2_2") (pintype "passive"))
      (node (ref "R87") (pin "2") (pinfunction "2_2") (pintype "passive"))
      (node (ref "U4") (pin "1") (pinfunction "EN_1") (pintype "input"))
      (node (ref "U4") (pin "2") (pinfunction "VDDPECL_2_2") (pintype "power_in"))
      (node (ref "U4") (pin "5") (pinfunction "VDDPECL_5") (pintype "power_in"))
    )
    (net (code "3") (name "/ADCCLK_N") (class "Default")
      (node (ref "U2") (pin "17") (pinfunction "U2N_17") (pintype "output"))
    )
    (net (code "4") (name "/ADCCLK_P") (class "Default")
      (node (ref "U2") (pin "16") (pinfunction "U2P_16") (pintype "output"))
    )
    (net (code "5") (name "/FPGA_CLK_N") (class "Default")
      (node (ref "U2") (pin "7") (pinfunction "U4N_7") (pintype "output"))
    )
    (net (code "6") (name "/FPGA_CLK_P") (class "Default")
      (node (ref "U2") (pin "6") (pinfunction "U4P_6") (pintype "output"))
    )
    (net (code "7") (name "/JX1_DACCLK_DAC1_N") (class "Default")
      (node (ref "R115") (pin "2") (pinfunction "2_2") (pintype "passive"))
      (node (ref "U2") (pin "28") (pinfunction "U0N_28") (pintype "output"))
    )
    (net (code "8") (name "/JX1_DACCLK_DAC1_P") (class "Default")
      (node (ref "R114") (pin "2") (pinfunction "2_2") (pintype "passive"))
      (node (ref "U2") (pin "27") (pinfunction "U0P_27") (pintype "output"))
    )
    (net (code "9") (name "/JX2_DACCLK_DAC2_N") (class "Default")
      (node (ref "U2") (pin "20") (pinfunction "U1N_20") (pintype "output"))
    )
    (net (code "10") (name "/JX2_DACCLK_DAC2_P") (class "Default")
      (node (ref "U2") (pin "19") (pinfunction "U1P_19") (pintype "output"))
    )
    (net (code "11") (name "/OSTR_DAC2_BUF_N") (class "Default")
      (node (ref "R116") (pin "1") (pinfunction "1_1") (pintype "passive"))
      (node (ref "R119") (pin "2") (pinfunction "2_2") (pintype "passive"))
      (node (ref "U4") (pin "10") (pinfunction "~{Y2}_10") (pintype "output"))
    )
    (net (code "12") (name "/OSTR_DAC2_BUF_P") (class "Default")
      (node (ref "R117") (pin "1") (pinfunction "1_1") (pintype "passive"))
      (node (ref "R118") (pin "2") (pinfunction "2_2") (pintype "passive"))
      (node (ref "U4") (pin "9") (pinfunction "Y2_9") (pintype "output"))
    )
    (net (code "13") (name "/OSTR_DAC_BUF_N") (class "Default")
      (node (ref "R86") (pin "1") (pinfunction "1_1") (pintype "passive"))
      (node (ref "R90") (pin "2") (pinfunction "2_2") (pintype "passive"))
      (node (ref "U4") (pin "16") (pinfunction "~{Y1}_16") (pintype "output"))
    )
    (net (code "14") (name "/OSTR_DAC_BUF_P") (class "Default")
      (node (ref "R87") (pin "1") (pinfunction "1_1") (pintype "passive"))
      (node (ref "R89") (pin "2") (pinfunction "2_2") (pintype "passive"))
      (node (ref "U4") (pin "15") (pinfunction "Y1_15") (pintype "output"))
    )
    (net (code "15") (name "/OSTR_DAC_N") (class "Default")
      (node (ref "C276") (pin "1") (pinfunction "1_1") (pintype "passive"))
      (node (ref "R113") (pin "2") (pinfunction "2_2") (pintype "passive"))
      (node (ref "U2") (pin "10") (pinfunction "U3N_10") (pintype "output"))
    )
    (net (code "16") (name "/OSTR_DAC_P") (class "Default")
      (node (ref "C274") (pin "1") (pinfunction "1_1") (pintype "passive"))
      (node (ref "R112") (pin "2") (pinfunction "2_2") (pintype "passive"))
      (node (ref "U2") (pin "9") (pinfunction "U3P_9") (pintype "output"))
    )
    (net (code "17") (name "/PRI_N") (class "Default")
      (node (ref "P8") (pin "2") (pinfunction "2_2") (pintype "passive"))
      (node (ref "U2") (pin "46") (pinfunction "PRI_REF-_46") (pintype "input"))
    )
    (net (code "18") (name "/PRI_P") (class "Default")
      (node (ref "C23") (pin "1") (pinfunction "1_1") (pintype "passive"))
      (node (ref "R25") (pin "1") (pinfunction "1_1") (pintype "passive"))
      (node (ref "R26") (pin "2") (pinfunction "2_2") (pintype "passive"))
      (node (ref "U2") (pin "45") (pinfunction "PRI_REF+_45") (pintype "input"))
    )
    (net (code "19") (name "/Power_Down") (class "Default")
      (node (ref "P9") (pin "2") (pinfunction "2_2") (pintype "passive"))
      (node (ref "U2") (pin "12") (pinfunction "~{Power_Down}_12") (pintype "input"))
    )
    (net (code "20") (name "/S0_1") (class "Default")
      (node (ref "P15") (pin "2") (pinfunction "2_2") (pintype "passive"))
      (node (ref "U4") (pin "18") (pinfunction "S0_18") (pintype "input"))
    )
    (net (code "21") (name "/S1_1") (class "Default")
      (node (ref "P14") (pin "2") (pinfunction "2_2") (pintype "passive"))
      (node (ref "U4") (pin "19") (pinfunction "S1_19") (pintype "input"))
    )
    (net (code "22") (name "/S2_1") (class "Default")
      (node (ref "P13") (pin "2") (pinfunction "2_2") (pintype "passive"))
      (node (ref "U4") (pin "24") (pinfunction "S2_24") (pintype "input"))
    )
    (net (code "23") (name "/SDO") (class "Default")
      (node (ref "U2") (pin "23") (pinfunction "SPI_MOSI_23") (pintype "input"))
    )
    (net (code "24") (name "/SPI_CLK") (class "Default")
      (node (ref "U2") (pin "24") (pinfunction "SPI_CLK_24") (pintype "input"))
    )
    (net (code "25") (name "/SPI_LE") (class "Default")
      (node (ref "U2") (pin "25") (pinfunction "SPI_LE_25") (pintype "input"))
    )
    (net (code "26") (name "/SPI_MISO") (class "Default")
      (node (ref "U2") (pin "22") (pinfunction "SPI_MISO_22") (pintype "output"))
    )
    (net (code "27") (name "/SYNC") (class "Default")
      (node (ref "J25") (pin "1") (pinfunction "1_1") (pintype "passive"))
      (node (ref "U2") (pin "14") (pinfunction "~{SYNC}_14") (pintype "input"))
    )
    (net (code "28") (name "/TEST_MODE") (class "Default")
      (node (ref "U2") (pin "33") (pinfunction "TEST_MODE_33") (pintype "input"))
    )
    (net (code "29") (name "/TEST_OUTA") (class "Default")
      (node (ref "R126") (pin "1") (pinfunction "1_1") (pintype "passive"))
      (node (ref "U2") (pin "30") (pinfunction "TESTOUTA_30") (pintype "passive"))
    )
    (net (code "30") (name "/VBB") (class "Default")
      (node (ref "C269") (pin "1") (pinfunction "1_1") (pintype "passive"))
      (node (ref "R92") (pin "2") (pinfunction "2_2") (pintype "passive"))
      (node (ref "U2") (pin "48") (pinfunction "VBB_48") (pintype "passive"))
      (node (ref "U4") (pin "6") (pinfunction "VBB_6") (pintype "output"))
    )
    (net (code "31") (name "/VCC1_PLL") (class "Default")
      (node (ref "C28") (pin "1") (pinfunction "1_1") (pintype "passive"))
      (node (ref "C29") (pin "1") (pinfunction "1_1") (pintype "passive"))
      (node (ref "C314") (pin "1") (pinfunction "1_1") (pintype "passive"))
      (node (ref "C315") (pin "1") (pinfunction "1_1") (pintype "passive"))
      (node (ref "FB5") (pin "2") (pinfunction "2_2") (pintype "passive"))
      (node (ref "U2") (pin "39") (pinfunction "VCC2_PLL_39") (pintype "power_in"))
      (node (ref "U2") (pin "42") (pinfunction "VCC2_PLL_42") (pintype "power_in"))
      (node (ref "U2") (pin "5") (pinfunction "VCC1_PLL_5") (pintype "power_in"))
    )
    (net (code "32") (name "/VCC_AUX_IN") (class "Default")
      (node (ref "C17") (pin "1") (pinfunction "1_1") (pintype "passive"))
      (node (ref "C18") (pin "1") (pinfunction "1_1") (pintype "passive"))
      (node (ref "FB2") (pin "2") (pinfunction "2_2") (pintype "passive"))
      (node (ref "U2") (pin "44") (pinfunction "VCC_AUXIN_44") (pintype "power_in"))
    )
    (net (code "33") (name "/VCC_AUX_OUT") (class "Default")
      (node (ref "C15") (pin "1") (pinfunction "1_1") (pintype "passive"))
      (node (ref "C16") (pin "1") (pinfunction "1_1") (pintype "passive"))
      (node (ref "FB1") (pin "2") (pinfunction "2_2") (pintype "passive"))
      (node (ref "U2") (pin "15") (pinfunction "VCC_AUXOUT_15") (pintype "power_in"))
    )
    (net (code "34") (name "/VCC_IN_PRI") (class "Default")
      (node (ref "C31") (pin "1") (pinfunction "1_1") (pintype "passive"))
      (node (ref "C32") (pin "1") (pinfunction "1_1") (pintype "passive"))
      (node (ref "FB6") (pin "2") (pinfunction "2_2") (pintype "passive"))
      (node (ref "U2") (pin "1") (pinfunction "VCC_IN_SEC_1") (pintype "power_in"))
      (node (ref "U2") (pin "47") (pinfunction "VCC_IN_PRI_47") (pintype "power_in"))
    )
    (net (code "35") (name "/VCC_OUT") (class "Default")
      (node (ref "C24") (pin "1") (pinfunction "1_1") (pintype "passive"))
      (node (ref "C25") (pin "1") (pinfunction "1_1") (pintype "passive"))
      (node (ref "C26") (pin "1") (pinfunction "1_1") (pintype "passive"))
      (node (ref "C27") (pin "1") (pinfunction "1_1") (pintype "passive"))
      (node (ref "C309") (pin "1") (pinfunction "1_1") (pintype "passive"))
      (node (ref "C310") (pin "1") (pinfunction "1_1") (pintype "passive"))
      (node (ref "C312") (pin "1") (pinfunction "1_1") (pintype "passive"))
      (node (ref "C313") (pin "1") (pinfunction "1_1") (pintype "passive"))
      (node (ref "FB4") (pin "2") (pinfunction "2_2") (pintype "passive"))
      (node (ref "U2") (pin "11") (pinfunction "VCC_OUT_11") (pintype "power_in"))
      (node (ref "U2") (pin "18") (pinfunction "VCC_OUT_18") (pintype "power_in"))
      (node (ref "U2") (pin "21") (pinfunction "VCC_OUT_21") (pintype "power_in"))
      (node (ref "U2") (pin "26") (pinfunction "VCC_OUT_26") (pintype "power_in"))
      (node (ref "U2") (pin "29") (pinfunction "VCC_OUT_29") (pintype "power_in"))
      (node (ref "U2") (pin "32") (pinfunction "VCC_OUT_32") (pintype "power_in"))
      (node (ref "U2") (pin "8") (pinfunction "VCC_OUT_8") (pintype "power_in"))
    )
    (net (code "36") (name "/VCC_VCO") (class "Default")
      (node (ref "C12") (pin "1") (pinfunction "1_1") (pintype "passive"))
      (node (ref "C20") (pin "1") (pinfunction "1_1") (pintype "passive"))
      (node (ref "C21") (pin "1") (pinfunction "1_1") (pintype "passive"))
      (node (ref "C22") (pin "1") (pinfunction "1_1") (pintype "passive"))
      (node (ref "FB3") (pin "2") (pinfunction "2_2") (pintype "passive"))
      (node (ref "U2") (pin "34") (pinfunction "VCC_VCO_34") (pintype "power_in"))
      (node (ref "U2") (pin "35") (pinfunction "VCC_VCO_35") (pintype "power_in"))
    )
    (net (code "37") (name "/VDD") (class "Default")
      (node (ref "C265") (pin "1") (pinfunction "1_1") (pintype "passive"))
      (node (ref "C306") (pin "1") (pinfunction "1_1") (pintype "passive"))
      (node (ref "FB25") (pin "2") (pinfunction "2_2") (pintype "passive"))
      (node (ref "U4") (pin "11") (pinfunction "VDD2_11") (pintype "power_in"))
      (node (ref "U4") (pin "14") (pinfunction "VDD1_2_14") (pintype "power_in"))
      (node (ref "U4") (pin "17") (pinfunction "VDD1_17") (pintype "power_in"))
      (node (ref "U4") (pin "8") (pinfunction "VDD2_2_8") (pintype "power_in"))
    )
    (net (code "38") (name "GND") (class "Default")
      (node (ref "C12") (pin "2") (pinfunction "2_2") (pintype "passive"))
      (node (ref "C15") (pin "2") (pinfunction "2_2") (pintype "passive"))
      (node (ref "C16") (pin "2") (pinfunction "2_2") (pintype "passive"))
      (node (ref "C17") (pin "2") (pinfunction "2_2") (pintype "passive"))
      (node (ref "C18") (pin "2") (pinfunction "2_2") (pintype "passive"))
      (node (ref "C20") (pin "2") (pinfunction "2_2") (pintype "passive"))
      (node (ref "C21") (pin "2") (pinfunction "2_2") (pintype "passive"))
      (node (ref "C22") (pin "2") (pinfunction "2_2") (pintype "passive"))
      (node (ref "C24") (pin "2") (pinfunction "2_2") (pintype "passive"))
      (node (ref "C25") (pin "2") (pinfunction "2_2") (pintype "passive"))
      (node (ref "C26") (pin "2") (pinfunction "2_2") (pintype "passive"))
      (node (ref "C265") (pin "2") (pinfunction "2_2") (pintype "passive"))
      (node (ref "C267") (pin "1") (pinfunction "1_1") (pintype "passive"))
      (node (ref "C268") (pin "1") (pinfunction "1_1") (pintype "passive"))
      (node (ref "C269") (pin "2") (pinfunction "2_2") (pintype "passive"))
      (node (ref "C27") (pin "2") (pinfunction "2_2") (pintype "passive"))
      (node (ref "C270") (pin "2") (pinfunction "2_2") (pintype "passive"))
      (node (ref "C271") (pin "2") (pinfunction "2_2") (pintype "passive"))
      (node (ref "C272") (pin "2") (pinfunction "2_2") (pintype "passive"))
      (node (ref "C273") (pin "2") (pinfunction "2_2") (pintype "passive"))
      (node (ref "C275") (pin "1") (pinfunction "1_1") (pintype "passive"))
      (node (ref "C28") (pin "2") (pinfunction "2_2") (pintype "passive"))
      (node (ref "C29") (pin "2") (pinfunction "2_2") (pintype "passive"))
      (node (ref "C306") (pin "2") (pinfunction "2_2") (pintype "passive"))
      (node (ref "C309") (pin "2") (pinfunction "2_2") (pintype "passive"))
      (node (ref "C31") (pin "2") (pinfunction "2_2") (pintype "passive"))
      (node (ref "C310") (pin "2") (pinfunction "2_2") (pintype "passive"))
      (node (ref "C311") (pin "2") (pinfunction "2_2") (pintype "passive"))
      (node (ref "C312") (pin "2") (pinfunction "2_2") (pintype "passive"))
      (node (ref "C313") (pin "2") (pinfunction "2_2") (pintype "passive"))
      (node (ref "C314") (pin "2") (pinfunction "2_2") (pintype "passive"))
      (node (ref "C315") (pin "2") (pinfunction "2_2") (pintype "passive"))
      (node (ref "C32") (pin "2") (pinfunction "2_2") (pintype "passive"))
      (node (ref "D1") (pin "1") (pinfunction "C_1") (pintype "passive"))
      (node (ref "J25") (pin "2") (pinfunction "MNT_1_2") (pintype "passive"))
      (node (ref "J3") (pin "2") (pinfunction "MNT_1_2") (pintype "passive"))
      (node (ref "J3") (pin "3") (pinfunction "MNT_2_3") (pintype "passive"))
      (node (ref "J5") (pin "2") (pinfunction "2_2") (pintype "passive"))
      (node (ref "J5") (pin "3") (pinfunction "3_3") (pintype "passive"))
      (node (ref "J5") (pin "4") (pinfunction "4_4") (pintype "passive"))
      (node (ref "J5") (pin "5") (pinfunction "5_5") (pintype "passive"))
      (node (ref "P13") (pin "3") (pinfunction "3_3") (pintype "passive"))
      (node (ref "P14") (pin "3") (pinfunction "3_3") (pintype "passive"))
      (node (ref "P15") (pin "3") (pinfunction "3_3") (pintype "passive"))
      (node (ref "P8") (pin "1") (pinfunction "1_1") (pintype "passive"))
      (node (ref "P9") (pin "3") (pinfunction "3_3") (pintype "passive"))
      (node (ref "R112") (pin "1") (pinfunction "1_1") (pintype "passive"))
      (node (ref "R113") (pin "1") (pinfunction "1_1") (pintype "passive"))
      (node (ref "R114") (pin "1") (pinfunction "1_1") (pintype "passive"))
      (node (ref "R115") (pin "1") (pinfunction "1_1") (pintype "passive"))
      (node (ref "R118") (pin "1") (pinfunction "1_1") (pintype "passive"))
      (node (ref "R119") (pin "1") (pinfunction "1_1") (pintype "passive"))
      (node (ref "R126") (pin "2") (pinfunction "2_2") (pintype "passive"))
      (node (ref "R24") (pin "1") (pinfunction "1_1") (pintype "passive"))
      (node (ref "R26") (pin "1") (pinfunction "1_1") (pintype "passive"))
      (node (ref "R27") (pin "1") (pinfunction "1_1") (pintype "passive"))
      (node (ref "R29") (pin "1") (pinfunction "1_1") (pintype "passive"))
      (node (ref "R85") (pin "1") (pinfunction "1_1") (pintype "passive"))
      (node (ref "R89") (pin "1") (pinfunction "1_1") (pintype "passive"))
      (node (ref "R90") (pin "1") (pinfunction "1_1") (pintype "passive"))
      (node (ref "R96") (pin "1") (pinfunction "1_1") (pintype "passive"))
      (node (ref "R97") (pin "1") (pinfunction "1_1") (pintype "passive"))
      (node (ref "R98") (pin "1") (pinfunction "1_1") (pintype "passive"))
      (node (ref "U2") (pin "2") (pinfunction "SEC_REF-_2") (pintype "passive"))
      (node (ref "U2") (pin "36") (pinfunction "GND_VCO_36") (pintype "power_in"))
      (node (ref "U2") (pin "43") (pinfunction "AUX_IN_43") (pintype "input"))
      (node (ref "U2") (pin "49") (pinfunction "GND_49") (pintype "power_in"))
      (node (ref "U4") (pin "13") (pinfunction "VSS_13") (pintype "passive"))
      (node (ref "U4") (pin "20") (pinfunction "VDD0_2_20") (pintype "power_in"))
      (node (ref "U4") (pin "23") (pinfunction "VDD0_23") (pintype "power_in"))
      (node (ref "U4") (pin "25") (pinfunction "EP_25") (pintype "passive"))
      (node (ref "U4") (pin "7") (pinfunction "VSS_2_7") (pintype "passive"))
    )
    (net (code "39") (name "Net-(C23-Pad2)") (class "Default")
      (node (ref "C23") (pin "2") (pinfunction "2_2") (pintype "passive"))
      (node (ref "J5") (pin "1") (pinfunction "1_1") (pintype "passive"))
      (node (ref "R27") (pin "2") (pinfunction "2_2") (pintype "passive"))
    )
    (net (code "40") (name "Net-(C30-Pad1)") (class "Default")
      (node (ref "C30") (pin "1") (pinfunction "1_1") (pintype "passive"))
      (node (ref "R30") (pin "2") (pinfunction "2_2") (pintype "passive"))
    )
    (net (code "41") (name "Net-(C275-Pad2)") (class "Default")
      (node (ref "C275") (pin "2") (pinfunction "2_2") (pintype "passive"))
      (node (ref "R91") (pin "1") (pinfunction "1_1") (pintype "passive"))
      (node (ref "R92") (pin "1") (pinfunction "1_1") (pintype "passive"))
      (node (ref "R93") (pin "2") (pinfunction "2_2") (pintype "passive"))
    )
    (net (code "42") (name "Net-(D1-A)") (class "Default")
      (node (ref "D1") (pin "2") (pinfunction "A_2") (pintype "passive"))
      (node (ref "R31") (pin "2") (pinfunction "2_2") (pintype "passive"))
    )
    (net (code "43") (name "Net-(P8-Pad3)") (class "Default")
      (node (ref "P8") (pin "3") (pinfunction "3_3") (pintype "passive"))
      (node (ref "R28") (pin "1") (pinfunction "1_1") (pintype "passive"))
      (node (ref "R29") (pin "2") (pinfunction "2_2") (pintype "passive"))
    )
    (net (code "44") (name "Net-(P9-Pad1)") (class "Default")
      (node (ref "P9") (pin "1") (pinfunction "1_1") (pintype "passive"))
      (node (ref "R84") (pin "1") (pinfunction "1_1") (pintype "passive"))
      (node (ref "R85") (pin "2") (pinfunction "2_2") (pintype "passive"))
    )
    (net (code "45") (name "Net-(P13-Pad1)") (class "Default")
      (node (ref "P13") (pin "1") (pinfunction "1_1") (pintype "passive"))
      (node (ref "R88") (pin "1") (pinfunction "1_1") (pintype "passive"))
      (node (ref "R96") (pin "2") (pinfunction "2_2") (pintype "passive"))
    )
    (net (code "46") (name "Net-(P14-Pad1)") (class "Default")
      (node (ref "P14") (pin "1") (pinfunction "1_1") (pintype "passive"))
      (node (ref "R94") (pin "1") (pinfunction "1_1") (pintype "passive"))
      (node (ref "R97") (pin "2") (pinfunction "2_2") (pintype "passive"))
    )
    (net (code "47") (name "Net-(P15-Pad1)") (class "Default")
      (node (ref "P15") (pin "1") (pinfunction "1_1") (pintype "passive"))
      (node (ref "R95") (pin "1") (pinfunction "1_1") (pintype "passive"))
      (node (ref "R98") (pin "2") (pinfunction "2_2") (pintype "passive"))
    )
    (net (code "48") (name "Net-(U2-EXT_LFN)") (class "Default")
      (node (ref "C30") (pin "2") (pinfunction "2_2") (pintype "passive"))
      (node (ref "C33") (pin "2") (pinfunction "2_2") (pintype "passive"))
      (node (ref "U2") (pin "41") (pinfunction "EXT_LFN_41") (pintype "passive"))
    )
    (net (code "49") (name "Net-(U2-EXT_LFP)") (class "Default")
      (node (ref "C33") (pin "1") (pinfunction "1_1") (pintype "passive"))
      (node (ref "R30") (pin "1") (pinfunction "1_1") (pintype "passive"))
      (node (ref "U2") (pin "40") (pinfunction "EXT_LFP_40") (pintype "passive"))
    )
    (net (code "50") (name "Net-(U2-PLL_LOCK)") (class "Default")
      (node (ref "R31") (pin "1") (pinfunction "1_1") (pintype "passive"))
      (node (ref "U2") (pin "37") (pinfunction "PLL_LOCK_37") (pintype "output"))
    )
    (net (code "51") (name "Net-(U2-REF_SEL)") (class "Default")
      (node (ref "J3") (pin "1") (pinfunction "1_1") (pintype "passive"))
      (node (ref "U2") (pin "31") (pinfunction "REF_SEL_31") (pintype "input"))
    )
    (net (code "52") (name "Net-(U2-REG_CAP1)") (class "Default")
      (node (ref "C267") (pin "2") (pinfunction "2_2") (pintype "passive"))
      (node (ref "U2") (pin "4") (pinfunction "REG_CAP1_4") (pintype "passive"))
    )
    (net (code "53") (name "Net-(U2-REG_CAP2)") (class "Default")
      (node (ref "C268") (pin "2") (pinfunction "2_2") (pintype "passive"))
      (node (ref "U2") (pin "38") (pinfunction "REG_CAP2_38") (pintype "passive"))
    )
    (net (code "54") (name "Net-(U2-SEC_REF+)") (class "Default")
      (node (ref "C14") (pin "2") (pinfunction "2_2") (pintype "passive"))
      (node (ref "R23") (pin "1") (pinfunction "1_1") (pintype "passive"))
      (node (ref "R24") (pin "2") (pinfunction "2_2") (pintype "passive"))
      (node (ref "U2") (pin "3") (pinfunction "SEC_REF+_3") (pintype "passive"))
    )
    (net (code "55") (name "Net-(U4-IN)") (class "Default")
      (node (ref "C274") (pin "2") (pinfunction "2_2") (pintype "passive"))
      (node (ref "R91") (pin "2") (pinfunction "2_2") (pintype "passive"))
      (node (ref "U4") (pin "3") (pinfunction "IN_3") (pintype "input"))
    )
    (net (code "56") (name "Net-(U4-~{IN})") (class "Default")
      (node (ref "C276") (pin "2") (pinfunction "2_2") (pintype "passive"))
      (node (ref "R93") (pin "1") (pinfunction "1_1") (pintype "passive"))
      (node (ref "U4") (pin "4") (pinfunction "~{IN}_4") (pintype "input"))
    )
    (net (code "57") (name "Net-(Y1-GND{slash}Case)") (class "Default")
      (node (ref "C13") (pin "2") (pinfunction "2_2") (pintype "passive"))
      (node (ref "Y1") (pin "2") (pinfunction "GND/Case_2") (pintype "power_in"))
    )
    (net (code "58") (name "Net-(Y1-Output)") (class "Default")
      (node (ref "C13") (pin "1") (pinfunction "1_1") (pintype "passive"))
      (node (ref "C14") (pin "1") (pinfunction "1_1") (pintype "passive"))
      (node (ref "Y1") (pin "3") (pinfunction "Output_3") (pintype "output"))
    )
    (net (code "59") (name "Net-(Y1-~{STBY})") (class "Default")
      (node (ref "P2") (pin "1") (pinfunction "1_1") (pintype "passive"))
      (node (ref "Y1") (pin "1") (pinfunction "~{STBY}_1") (pintype "input"))
    )
    (net (code "60") (name "unconnected-(U2-AUX_OUT-Pad13)") (class "Default")
      (node (ref "U2") (pin "13") (pinfunction "AUX_OUT_13") (pintype "output"))
    )
    (net (code "61") (name "unconnected-(U4-NC-Pad12)") (class "Default")
      (node (ref "U4") (pin "12") (pinfunction "NC_12") (pintype "passive"))
    )
    (net (code "62") (name "unconnected-(U4-Y0-Pad21)") (class "Default")
      (node (ref "U4") (pin "21") (pinfunction "Y0_21") (pintype "output"))
    )
    (net (code "63") (name "unconnected-(U4-~{Y0}-Pad22)") (class "Default")
      (node (ref "U4") (pin "22") (pinfunction "~{Y0}_22") (pintype "output"))
    )
  )
)
